# TSOC_USBUART2_R5_1.net
KiCad netlist of a schematic drawn in EAGLE
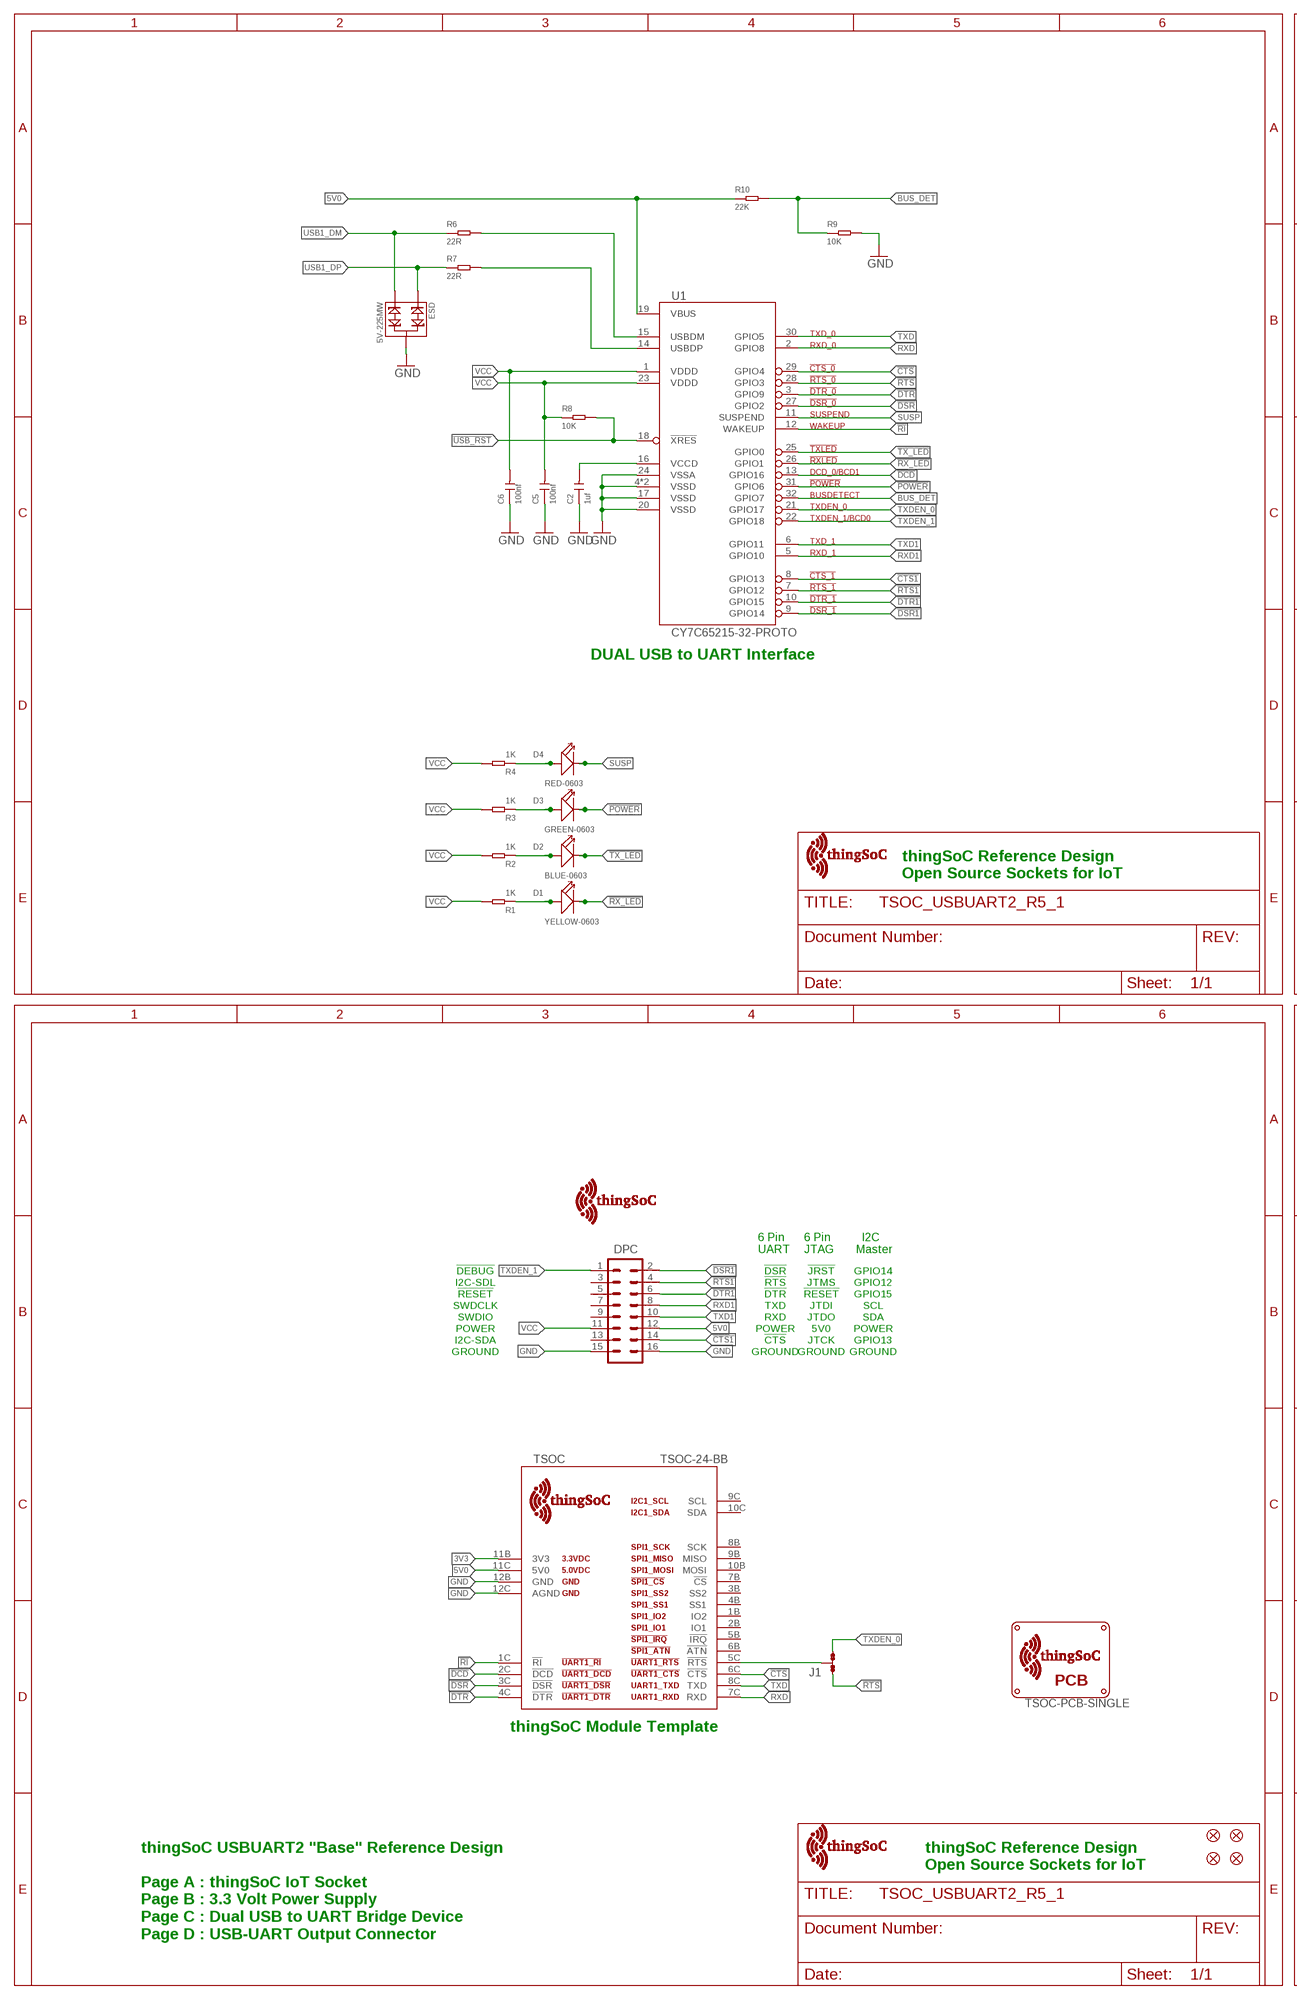
[diagram p0: schematic, sheet 1, part 1 of 2]
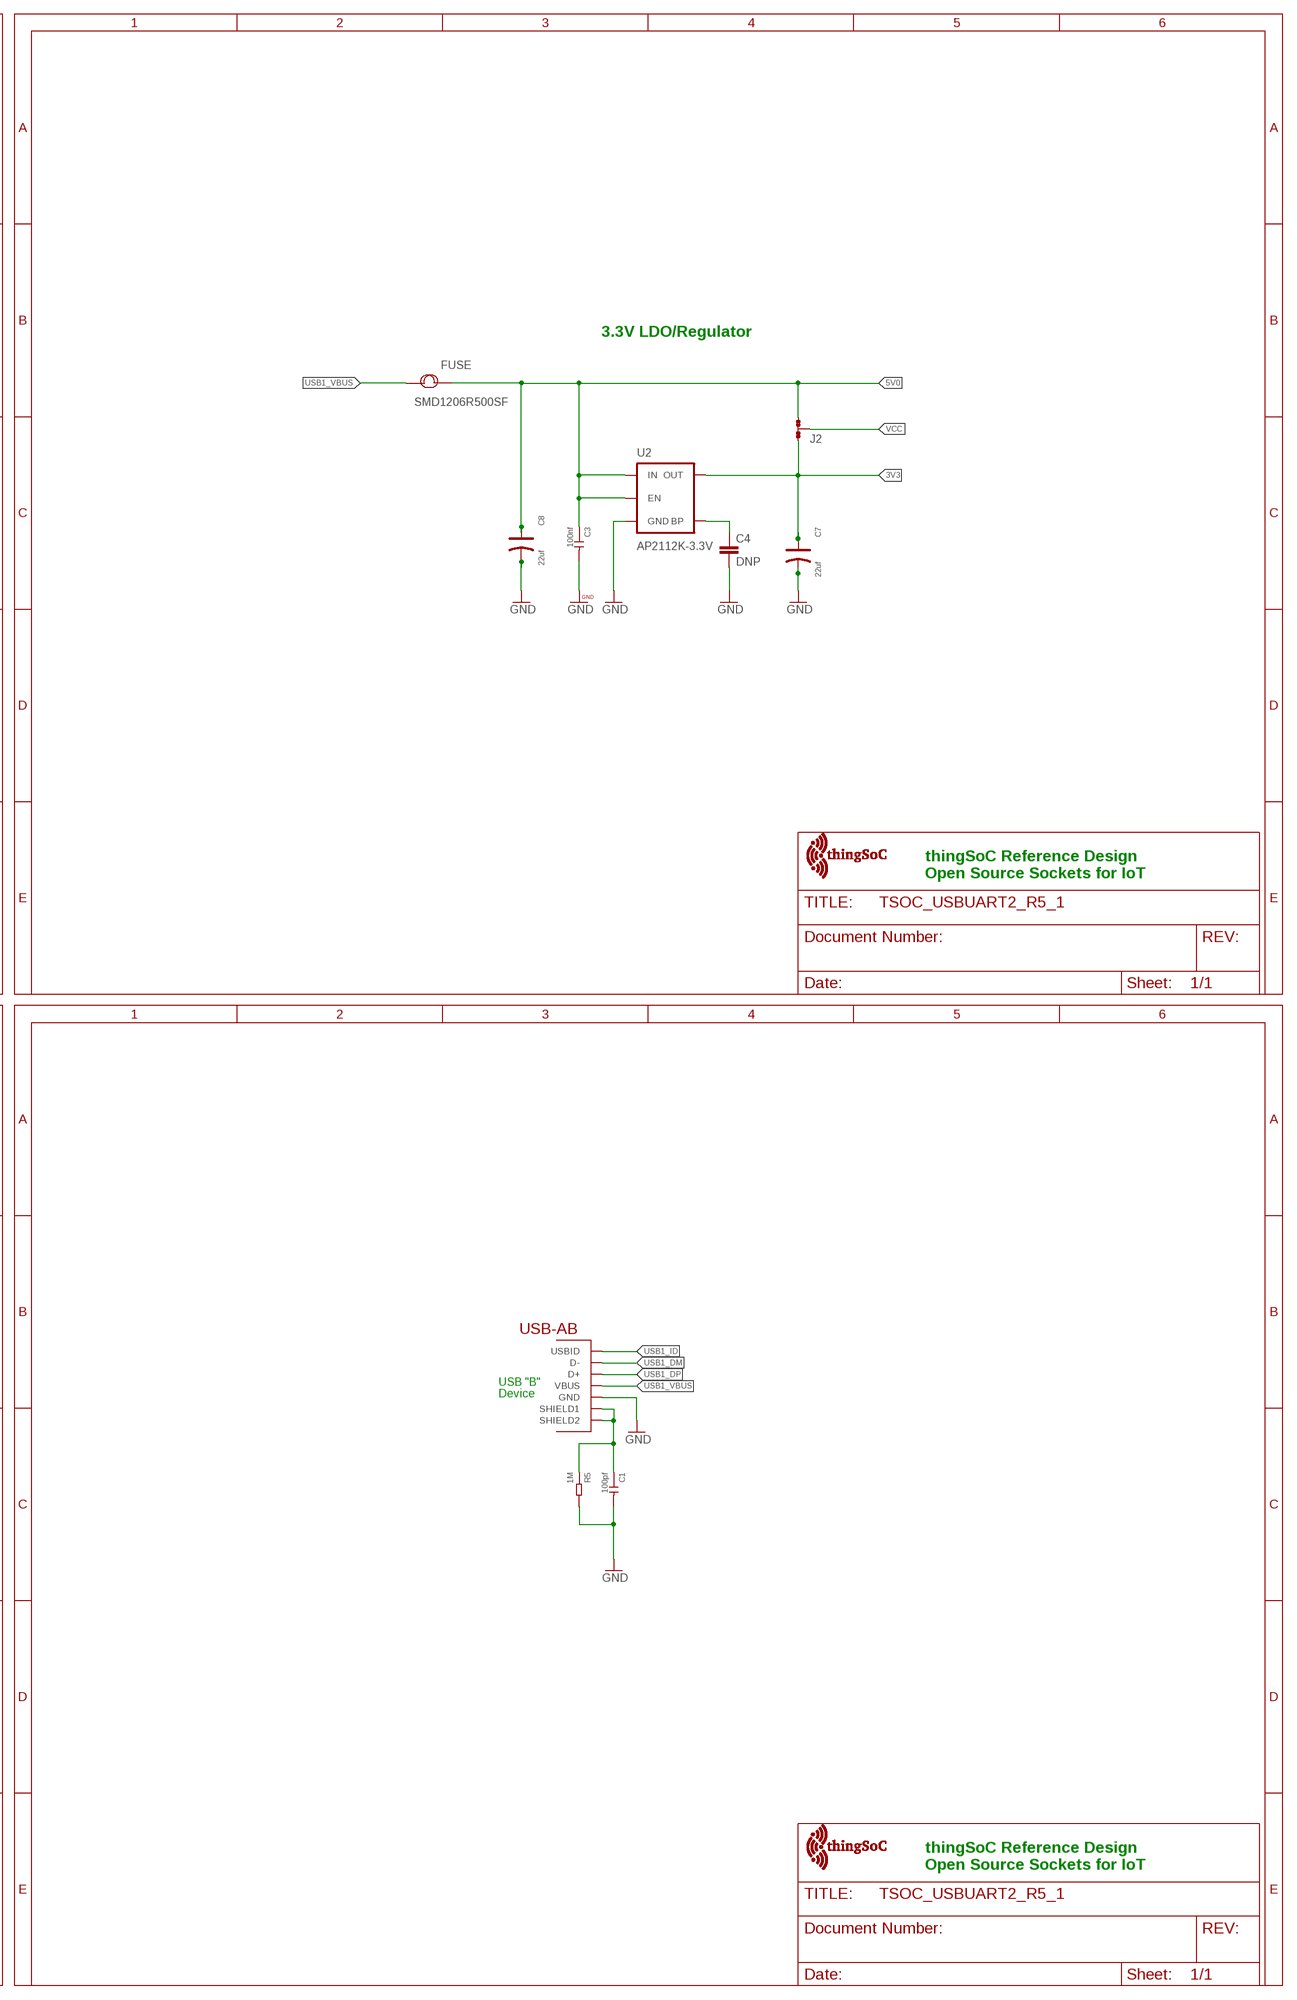
[diagram p1: schematic, sheet 1, part 2 of 2]

(export (version "E")
  (design (tool "Eeschema 10.0.6"))
  (components
    (comp (ref "$$U$2")
      (value "TSOC-LOGO")
      (footprint "eagle-import:TSOC-LOGO-BLANK")
      (libsource (lib "eagle-import") (part "TSOC-LOGO"))
    )
    (comp (ref "C1")
      (value "100pf")
      (footprint "eagle-import:C0603")
      (fields (field (name "MPN") "CC0603JRNPO9BN101"))
      (libsource (lib "eagle-import") (part "CERAMIC-100PF-50V-5%-NPO(0603)"))
    )
    (comp (ref "C2")
      (value "1uf")
      (footprint "eagle-import:C0603")
      (fields (field (name "MPN") "CC0603KRX7R8BB105"))
      (libsource (lib "eagle-import") (part "CERAMIC-1UF-25V-10%-X7R(0603)"))
    )
    (comp (ref "C3")
      (value "100nf")
      (footprint "eagle-import:C0603")
      (fields (field (name "MPN") "CC0603KRX7R9BB104"))
      (libsource (lib "eagle-import") (part "CERAMIC-100NF-50V-10%-X7R(0603)"))
    )
    (comp (ref "C4")
      (value "DNP")
      (footprint "eagle-import:EIA-0603")
      (libsource (lib "eagle-import") (part "CAP-0603"))
    )
    (comp (ref "C5")
      (value "100nf")
      (footprint "eagle-import:C0603")
      (fields (field (name "MPN") "CC0603KRX7R9BB104"))
      (libsource (lib "eagle-import") (part "CERAMIC-100NF-50V-10%-X7R(0603)"))
    )
    (comp (ref "C6")
      (value "100nf")
      (footprint "eagle-import:C0603")
      (fields (field (name "MPN") "CC0603KRX7R9BB104"))
      (libsource (lib "eagle-import") (part "CERAMIC-100NF-50V-10%-X7R(0603)"))
    )
    (comp (ref "C7")
      (value "22uf")
      (footprint "eagle-import:AVX-A")
      (fields (field (name "MPN") "TAJA226*010#NJ"))
      (libsource (lib "eagle-import") (part "TANTALUM-SMD-22UF-10V(AVX-A)"))
    )
    (comp (ref "C8")
      (value "22uf")
      (footprint "eagle-import:AVX-A")
      (fields (field (name "MPN") "TAJA226*010#NJ"))
      (libsource (lib "eagle-import") (part "TANTALUM-SMD-22UF-10V(AVX-A)"))
    )
    (comp (ref "D1")
      (value "YELLOW-0603")
      (footprint "eagle-import:LED-0603")
      (fields (field (name "MPN") "19-217-Y5C-AM1N1VY-3T"))
      (libsource (lib "eagle-import") (part "SMD-LED-CLEAR-YELLOW(0603)"))
    )
    (comp (ref "D2")
      (value "BLUE-0603")
      (footprint "eagle-import:LED-0603")
      (fields (field (name "MPN") "19-217-BHC-ZL1M2RY-3T"))
      (libsource (lib "eagle-import") (part "SMD-LED-CLEAR-BLUE(0603)"))
    )
    (comp (ref "D3")
      (value "GREEN-0603")
      (footprint "eagle-import:LED-0603")
      (fields (field (name "MPN") "19-217-G7C-AN1P2-3T"))
      (libsource (lib "eagle-import") (part "SMD-LED-CLEAR-GREEN(0603)"))
    )
    (comp (ref "D4")
      (value "RED-0603")
      (footprint "eagle-import:LED-0603")
      (fields (field (name "MPN") "19-217-R6C-AL1M2VY-3T"))
      (libsource (lib "eagle-import") (part "LED-SMD-RED-DIFFUSED(0603)"))
    )
    (comp (ref "DPC")
      (value "M08X2")
      (footprint "eagle-import:2X8")
      (libsource (lib "eagle-import") (part "M08X2"))
    )
    (comp (ref "ESD")
      (value "5V-225MW")
      (footprint "eagle-import:SOT-23")
      (fields (field (name "MPN") "CESD5V0AP"))
      (libsource (lib "eagle-import") (part "SMD-DIODE-TVS-5V-225MW(SOT-23)"))
    )
    (comp (ref "FID1")
      (value "FIDUCIALUFIDUCIAL")
      (footprint "eagle-import:MICRO-FIDUCIAL")
      (libsource (lib "eagle-import") (part "FIDUCIALUFIDUCIAL"))
    )
    (comp (ref "FID2")
      (value "FIDUCIALUFIDUCIAL")
      (footprint "eagle-import:MICRO-FIDUCIAL")
      (libsource (lib "eagle-import") (part "FIDUCIALUFIDUCIAL"))
    )
    (comp (ref "FID3")
      (value "FIDUCIALUFIDUCIAL")
      (footprint "eagle-import:MICRO-FIDUCIAL")
      (libsource (lib "eagle-import") (part "FIDUCIALUFIDUCIAL"))
    )
    (comp (ref "FID4")
      (value "FIDUCIALUFIDUCIAL")
      (footprint "eagle-import:MICRO-FIDUCIAL")
      (libsource (lib "eagle-import") (part "FIDUCIALUFIDUCIAL"))
    )
    (comp (ref "FUSE")
      (value "SMD1206R500SF")
      (footprint "eagle-import:F1206")
      (libsource (lib "eagle-import") (part "SMD-PPTC-500MA(1206)"))
    )
    (comp (ref "J1")
      (value "JMP-3-1_2")
      (footprint "eagle-import:JMP-3-1_2")
      (libsource (lib "eagle-import") (part "JMP-3-1_2"))
    )
    (comp (ref "J2")
      (value "JMP-3-1_2")
      (footprint "eagle-import:JMP-3-1_2")
      (libsource (lib "eagle-import") (part "JMP-3-1_2"))
    )
    (comp (ref "R1")
      (value "1K")
      (footprint "eagle-import:R0603")
      (fields (field (name "MPN") "RC0603FR-071KL"))
      (libsource (lib "eagle-import") (part "SMD-RES-1K-1%-1/10W(0603)"))
    )
    (comp (ref "R2")
      (value "1K")
      (footprint "eagle-import:R0603")
      (fields (field (name "MPN") "RC0603FR-071KL"))
      (libsource (lib "eagle-import") (part "SMD-RES-1K-1%-1/10W(0603)"))
    )
    (comp (ref "R3")
      (value "1K")
      (footprint "eagle-import:R0603")
      (fields (field (name "MPN") "RC0603FR-071KL"))
      (libsource (lib "eagle-import") (part "SMD-RES-1K-1%-1/10W(0603)"))
    )
    (comp (ref "R4")
      (value "1K")
      (footprint "eagle-import:R0603")
      (fields (field (name "MPN") "RC0603FR-071KL"))
      (libsource (lib "eagle-import") (part "SMD-RES-1K-1%-1/10W(0603)"))
    )
    (comp (ref "R5")
      (value "1M")
      (footprint "eagle-import:R0603")
      (fields (field (name "MPN") "RC0603FR-071ML"))
      (libsource (lib "eagle-import") (part "SMD-RES-1M-1%-1/10W(0603)"))
    )
    (comp (ref "R6")
      (value "22R")
      (footprint "eagle-import:R0603")
      (fields (field (name "MPN") "RC0603JR-0722RL"))
      (libsource (lib "eagle-import") (part "SMD-RES-22R-5%-1/10W(0603)"))
    )
    (comp (ref "R7")
      (value "22R")
      (footprint "eagle-import:R0603")
      (fields (field (name "MPN") "RC0603JR-0722RL"))
      (libsource (lib "eagle-import") (part "SMD-RES-22R-5%-1/10W(0603)"))
    )
    (comp (ref "R8")
      (value "10K")
      (footprint "eagle-import:R0603")
      (fields (field (name "MPN") "RC0603FR-0710KL"))
      (libsource (lib "eagle-import") (part "SMD-RES-10K-1%-1/10W(0603)"))
    )
    (comp (ref "R9")
      (value "10K")
      (footprint "eagle-import:R0603")
      (fields (field (name "MPN") "RC0603FR-0710KL"))
      (libsource (lib "eagle-import") (part "SMD-RES-10K-1%-1/10W(0603)"))
    )
    (comp (ref "R10")
      (value "22K")
      (footprint "eagle-import:R0603")
      (fields (field (name "MPN") "RC0603JR-0722KL"))
      (libsource (lib "eagle-import") (part "SMD-RES-22K-5%-1/10W(0603)"))
    )
    (comp (ref "TSOC")
      (value "TSOC-24-BB")
      (footprint "eagle-import:TSOC-BB-S24")
      (libsource (lib "eagle-import") (part "TSOC-24-BB"))
    )
    (comp (ref "U$1")
      (value "TSOC-LOGO")
      (footprint "eagle-import:TSOC-LOGO-BLANK")
      (libsource (lib "eagle-import") (part "TSOC-LOGO"))
    )
    (comp (ref "U$3")
      (value "TSOC-LOGO")
      (footprint "eagle-import:TSOC-LOGO-BLANK")
      (libsource (lib "eagle-import") (part "TSOC-LOGO"))
    )
    (comp (ref "U$4")
      (value "TSOC-PCB-SINGLE")
      (footprint "eagle-import:TSOC-BB-BRD-DIM")
      (libsource (lib "eagle-import") (part "TSOC-PCB-SINGLE"))
    )
    (comp (ref "U$7")
      (value "TSOC-LOGO-SMALL")
      (footprint "eagle-import:TSOC-LOGO-SML")
      (libsource (lib "eagle-import") (part "TSOC-LOGO-SMALL"))
    )
    (comp (ref "U$100")
      (value "TSOC-LOGO-LRG")
      (footprint "eagle-import:TSOC-LOGO-LRG")
      (libsource (lib "eagle-import") (part "TSOC-LOGO-LRG"))
    )
    (comp (ref "U1")
      (value "CY7C65215-32-PROTO")
      (footprint "eagle-import:QFN32-PROTO")
      (libsource (lib "eagle-import") (part "CY7C65215-32-PROTO"))
    )
    (comp (ref "U2")
      (value "AP2112K-3.3V")
      (footprint "eagle-import:SOT23-5")
      (libsource (lib "eagle-import") (part "V_REG_LDOSMD"))
    )
    (comp (ref "USB")
      (value "USB_AB")
      (footprint "eagle-import:USB-AB-MICRO-SMD")
      (libsource (lib "eagle-import") (part "USB_AB"))
    )
  )
  (nets
    (net (code "1") (name "/~{CTS1}") (class "Default")
      (node (ref "DPC") (pin "14") (pinfunction "14_14") (pintype "passive"))
      (node (ref "U1") (pin "8") (pinfunction "GPIO13_8") (pintype "input"))
    )
    (net (code "2") (name "/~{CTS}") (class "Default")
      (node (ref "TSOC") (pin "6C") (pinfunction "~{CTS}_6C") (pintype "bidirectional"))
      (node (ref "U1") (pin "29") (pinfunction "GPIO4_29") (pintype "input"))
    )
    (net (code "3") (name "/~{DCD}") (class "Default")
      (node (ref "TSOC") (pin "2C") (pinfunction "~{DCD}_2C") (pintype "bidirectional"))
      (node (ref "U1") (pin "13") (pinfunction "GPIO16_13") (pintype "output"))
    )
    (net (code "4") (name "/~{DSR1}") (class "Default")
      (node (ref "DPC") (pin "2") (pinfunction "2_2") (pintype "passive"))
      (node (ref "U1") (pin "9") (pinfunction "GPIO14_9") (pintype "input"))
    )
    (net (code "5") (name "/~{DSR}") (class "Default")
      (node (ref "TSOC") (pin "3C") (pinfunction "~{DSR}_3C") (pintype "bidirectional"))
      (node (ref "U1") (pin "27") (pinfunction "GPIO2_27") (pintype "input"))
    )
    (net (code "6") (name "/~{DTR1}") (class "Default")
      (node (ref "DPC") (pin "6") (pinfunction "6_6") (pintype "passive"))
      (node (ref "U1") (pin "10") (pinfunction "GPIO15_10") (pintype "output"))
    )
    (net (code "7") (name "/~{DTR}") (class "Default")
      (node (ref "TSOC") (pin "4C") (pinfunction "~{DTR}_4C") (pintype "bidirectional"))
      (node (ref "U1") (pin "3") (pinfunction "GPIO9_3") (pintype "output"))
    )
    (net (code "8") (name "/~{POWER}") (class "Default")
      (node (ref "D3") (pin "-") (pinfunction "-_-") (pintype "passive"))
      (node (ref "U1") (pin "31") (pinfunction "GPIO6_31") (pintype "input"))
    )
    (net (code "9") (name "/~{RI}") (class "Default")
      (node (ref "TSOC") (pin "1C") (pinfunction "~{RI}_1C") (pintype "bidirectional"))
      (node (ref "U1") (pin "12") (pinfunction "WAKEUP_12") (pintype "input"))
    )
    (net (code "10") (name "/~{RTS1}") (class "Default")
      (node (ref "DPC") (pin "4") (pinfunction "4_4") (pintype "passive"))
      (node (ref "U1") (pin "7") (pinfunction "GPIO12_7") (pintype "output"))
    )
    (net (code "11") (name "/~{RTS}") (class "Default")
      (node (ref "J1") (pin "1") (pinfunction "1_1") (pintype "passive"))
      (node (ref "U1") (pin "28") (pinfunction "GPIO3_28") (pintype "output"))
    )
    (net (code "12") (name "/~{RX_LED}") (class "Default")
      (node (ref "D1") (pin "-") (pinfunction "-_-") (pintype "passive"))
      (node (ref "U1") (pin "26") (pinfunction "GPIO1_26") (pintype "input"))
    )
    (net (code "13") (name "/~{TX_LED}") (class "Default")
      (node (ref "D2") (pin "-") (pinfunction "-_-") (pintype "passive"))
      (node (ref "U1") (pin "25") (pinfunction "GPIO0_25") (pintype "input"))
    )
    (net (code "14") (name "/~{USB_RST}") (class "Default")
      (node (ref "R8") (pin "2") (pinfunction "2_2") (pintype "passive"))
      (node (ref "U1") (pin "18") (pinfunction "~{XRES}_18") (pintype "input"))
    )
    (net (code "15") (name "3V3") (class "Default")
      (node (ref "C7") (pin "+") (pinfunction "+_+") (pintype "passive"))
      (node (ref "J2") (pin "1") (pinfunction "1_1") (pintype "passive"))
      (node (ref "TSOC") (pin "11B") (pinfunction "3V3_11B") (pintype "bidirectional"))
      (node (ref "U2") (pin "5") (pinfunction "OUT_5") (pintype "passive"))
    )
    (net (code "16") (name "5V0") (class "Default")
      (node (ref "C3") (pin "1") (pinfunction "1_1") (pintype "passive"))
      (node (ref "C8") (pin "+") (pinfunction "+_+") (pintype "passive"))
      (node (ref "DPC") (pin "12") (pinfunction "12_12") (pintype "passive"))
      (node (ref "FUSE") (pin "2") (pinfunction "2_2") (pintype "bidirectional"))
      (node (ref "J2") (pin "3") (pinfunction "3_3") (pintype "passive"))
      (node (ref "R10") (pin "1") (pinfunction "1_1") (pintype "passive"))
      (node (ref "TSOC") (pin "11C") (pinfunction "5V0_11C") (pintype "bidirectional"))
      (node (ref "U1") (pin "19") (pinfunction "VBUS_19") (pintype "power_in"))
      (node (ref "U2") (pin "1") (pinfunction "IN_1") (pintype "input"))
      (node (ref "U2") (pin "3") (pinfunction "EN_3") (pintype "input"))
    )
    (net (code "17") (name "BUS_DET") (class "Default")
      (node (ref "R10") (pin "2") (pinfunction "2_2") (pintype "passive"))
      (node (ref "R9") (pin "1") (pinfunction "1_1") (pintype "passive"))
      (node (ref "U1") (pin "32") (pinfunction "GPIO7_32") (pintype "input"))
    )
    (net (code "18") (name "GND") (class "Default")
      (node (ref "C1") (pin "2") (pinfunction "2_2") (pintype "passive"))
      (node (ref "C2") (pin "1") (pinfunction "1_1") (pintype "passive"))
      (node (ref "C3") (pin "2") (pinfunction "2_2") (pintype "passive"))
      (node (ref "C4") (pin "2") (pinfunction "2_2") (pintype "passive"))
      (node (ref "C5") (pin "1") (pinfunction "1_1") (pintype "passive"))
      (node (ref "C6") (pin "1") (pinfunction "1_1") (pintype "passive"))
      (node (ref "C7") (pin "-") (pinfunction "-_-") (pintype "passive"))
      (node (ref "C8") (pin "-") (pinfunction "-_-") (pintype "passive"))
      (node (ref "DPC") (pin "15") (pinfunction "15_15") (pintype "passive"))
      (node (ref "DPC") (pin "16") (pinfunction "16_16") (pintype "passive"))
      (node (ref "ESD") (pin "3") (pinfunction "3_3") (pintype "bidirectional"))
      (node (ref "R5") (pin "2") (pinfunction "2_2") (pintype "passive"))
      (node (ref "R9") (pin "2") (pinfunction "2_2") (pintype "passive"))
      (node (ref "TSOC") (pin "12B") (pinfunction "GND_12B") (pintype "bidirectional"))
      (node (ref "TSOC") (pin "12C") (pinfunction "AGND_12C") (pintype "bidirectional"))
      (node (ref "U1") (pin "17") (pinfunction "VSSD_17") (pintype "power_in"))
      (node (ref "U1") (pin "20") (pinfunction "VSSD_20") (pintype "power_in"))
      (node (ref "U1") (pin "24") (pinfunction "VSSA_24") (pintype "power_in"))
      (node (ref "U1") (pin "4") (pinfunction "VSSD_4") (pintype "power_in"))
      (node (ref "U1") (pin "EXP") (pinfunction "VSSD_EXP") (pintype "power_in"))
      (node (ref "U2") (pin "2") (pinfunction "GND_2") (pintype "input"))
      (node (ref "USB") (pin "GND") (pinfunction "GND_GND") (pintype "bidirectional"))
    )
    (net (code "19") (name "Net-(C1-Pad1)") (class "Default")
      (node (ref "C1") (pin "1") (pinfunction "1_1") (pintype "passive"))
      (node (ref "R5") (pin "1") (pinfunction "1_1") (pintype "passive"))
      (node (ref "USB") (pin "SHIELD1") (pinfunction "SHIELD1_SHIELD1") (pintype "bidirectional"))
      (node (ref "USB") (pin "SHIELD2") (pinfunction "SHIELD2_SHIELD2") (pintype "bidirectional"))
    )
    (net (code "20") (name "Net-(D1-Pad+)") (class "Default")
      (node (ref "D1") (pin "+") (pinfunction "+_+") (pintype "passive"))
      (node (ref "R1") (pin "1") (pinfunction "1_1") (pintype "passive"))
    )
    (net (code "21") (name "Net-(D2-Pad+)") (class "Default")
      (node (ref "D2") (pin "+") (pinfunction "+_+") (pintype "passive"))
      (node (ref "R2") (pin "1") (pinfunction "1_1") (pintype "passive"))
    )
    (net (code "22") (name "Net-(D3-Pad+)") (class "Default")
      (node (ref "D3") (pin "+") (pinfunction "+_+") (pintype "passive"))
      (node (ref "R3") (pin "1") (pinfunction "1_1") (pintype "passive"))
    )
    (net (code "23") (name "Net-(D4-Pad+)") (class "Default")
      (node (ref "D4") (pin "+") (pinfunction "+_+") (pintype "passive"))
      (node (ref "R4") (pin "1") (pinfunction "1_1") (pintype "passive"))
    )
    (net (code "24") (name "Net-(TSOC-~{RTS})") (class "Default")
      (node (ref "J1") (pin "2") (pinfunction "2_2") (pintype "passive"))
      (node (ref "TSOC") (pin "5C") (pinfunction "~{RTS}_5C") (pintype "bidirectional"))
    )
    (net (code "25") (name "Net-(U1-USBDM)") (class "Default")
      (node (ref "R6") (pin "2") (pinfunction "2_2") (pintype "passive"))
      (node (ref "U1") (pin "15") (pinfunction "USBDM_15") (pintype "bidirectional"))
    )
    (net (code "26") (name "Net-(U1-USBDP)") (class "Default")
      (node (ref "R7") (pin "2") (pinfunction "2_2") (pintype "passive"))
      (node (ref "U1") (pin "14") (pinfunction "USBDP_14") (pintype "bidirectional"))
    )
    (net (code "27") (name "Net-(U1-VCCD)") (class "Default")
      (node (ref "C2") (pin "2") (pinfunction "2_2") (pintype "passive"))
      (node (ref "U1") (pin "16") (pinfunction "VCCD_16") (pintype "output"))
    )
    (net (code "28") (name "Net-(U2-BP)") (class "Default")
      (node (ref "C4") (pin "1") (pinfunction "1_1") (pintype "passive"))
      (node (ref "U2") (pin "4") (pinfunction "BP_4") (pintype "input"))
    )
    (net (code "29") (name "RXD") (class "Default")
      (node (ref "TSOC") (pin "7C") (pinfunction "RXD_7C") (pintype "bidirectional"))
      (node (ref "U1") (pin "2") (pinfunction "GPIO8_2") (pintype "input"))
    )
    (net (code "30") (name "RXD1") (class "Default")
      (node (ref "DPC") (pin "8") (pinfunction "8_8") (pintype "passive"))
      (node (ref "U1") (pin "5") (pinfunction "GPIO10_5") (pintype "input"))
    )
    (net (code "31") (name "SUSP") (class "Default")
      (node (ref "D4") (pin "-") (pinfunction "-_-") (pintype "passive"))
      (node (ref "U1") (pin "11") (pinfunction "SUSPEND_11") (pintype "input"))
    )
    (net (code "32") (name "TXD") (class "Default")
      (node (ref "TSOC") (pin "8C") (pinfunction "TXD_8C") (pintype "bidirectional"))
      (node (ref "U1") (pin "30") (pinfunction "GPIO5_30") (pintype "output"))
    )
    (net (code "33") (name "TXD1") (class "Default")
      (node (ref "DPC") (pin "10") (pinfunction "10_10") (pintype "passive"))
      (node (ref "U1") (pin "6") (pinfunction "GPIO11_6") (pintype "output"))
    )
    (net (code "34") (name "TXDEN_0") (class "Default")
      (node (ref "J1") (pin "3") (pinfunction "3_3") (pintype "passive"))
      (node (ref "U1") (pin "21") (pinfunction "GPIO17_21") (pintype "input"))
    )
    (net (code "35") (name "TXDEN_1") (class "Default")
      (node (ref "DPC") (pin "1") (pinfunction "1_1") (pintype "passive"))
      (node (ref "U1") (pin "22") (pinfunction "GPIO18_22") (pintype "input"))
    )
    (net (code "36") (name "USB1_DM") (class "Default")
      (node (ref "ESD") (pin "2") (pinfunction "2_2") (pintype "power_in"))
      (node (ref "R6") (pin "1") (pinfunction "1_1") (pintype "passive"))
      (node (ref "USB") (pin "D-") (pinfunction "D-_D-") (pintype "bidirectional"))
    )
    (net (code "37") (name "USB1_DP") (class "Default")
      (node (ref "ESD") (pin "1") (pinfunction "1_1") (pintype "power_in"))
      (node (ref "R7") (pin "1") (pinfunction "1_1") (pintype "passive"))
      (node (ref "USB") (pin "D+") (pinfunction "D+_D+") (pintype "bidirectional"))
    )
    (net (code "38") (name "USB1_ID") (class "Default")
      (node (ref "USB") (pin "ID") (pinfunction "USBID_ID") (pintype "bidirectional"))
    )
    (net (code "39") (name "USB1_VBUS") (class "Default")
      (node (ref "FUSE") (pin "1") (pinfunction "1_1") (pintype "bidirectional"))
      (node (ref "USB") (pin "VBUS") (pinfunction "VBUS_VBUS") (pintype "bidirectional"))
    )
    (net (code "40") (name "VCC") (class "Default")
      (node (ref "C5") (pin "2") (pinfunction "2_2") (pintype "passive"))
      (node (ref "C6") (pin "2") (pinfunction "2_2") (pintype "passive"))
      (node (ref "DPC") (pin "11") (pinfunction "11_11") (pintype "passive"))
      (node (ref "J2") (pin "2") (pinfunction "2_2") (pintype "passive"))
      (node (ref "R1") (pin "2") (pinfunction "2_2") (pintype "passive"))
      (node (ref "R2") (pin "2") (pinfunction "2_2") (pintype "passive"))
      (node (ref "R3") (pin "2") (pinfunction "2_2") (pintype "passive"))
      (node (ref "R4") (pin "2") (pinfunction "2_2") (pintype "passive"))
      (node (ref "R8") (pin "1") (pinfunction "1_1") (pintype "passive"))
      (node (ref "U1") (pin "1") (pinfunction "VDDD_1") (pintype "power_in"))
      (node (ref "U1") (pin "23") (pinfunction "VDDD_23") (pintype "power_in"))
    )
    (net (code "41") (name "unconnected-(DPC-Pad3)") (class "Default")
      (node (ref "DPC") (pin "3") (pinfunction "3_3") (pintype "passive"))
    )
    (net (code "42") (name "unconnected-(DPC-Pad5)") (class "Default")
      (node (ref "DPC") (pin "5") (pinfunction "5_5") (pintype "passive"))
    )
    (net (code "43") (name "unconnected-(DPC-Pad7)") (class "Default")
      (node (ref "DPC") (pin "7") (pinfunction "7_7") (pintype "passive"))
    )
    (net (code "44") (name "unconnected-(DPC-Pad9)") (class "Default")
      (node (ref "DPC") (pin "9") (pinfunction "9_9") (pintype "passive"))
    )
    (net (code "45") (name "unconnected-(DPC-Pad13)") (class "Default")
      (node (ref "DPC") (pin "13") (pinfunction "13_13") (pintype "passive"))
    )
    (net (code "46") (name "unconnected-(TSOC-IO1-Pad2B)") (class "Default")
      (node (ref "TSOC") (pin "2B") (pinfunction "IO1_2B") (pintype "bidirectional"))
    )
    (net (code "47") (name "unconnected-(TSOC-IO2-Pad1B)") (class "Default")
      (node (ref "TSOC") (pin "1B") (pinfunction "IO2_1B") (pintype "bidirectional"))
    )
    (net (code "48") (name "unconnected-(TSOC-MISO-Pad9B)") (class "Default")
      (node (ref "TSOC") (pin "9B") (pinfunction "MISO_9B") (pintype "bidirectional"))
    )
    (net (code "49") (name "unconnected-(TSOC-MOSI-Pad10B)") (class "Default")
      (node (ref "TSOC") (pin "10B") (pinfunction "MOSI_10B") (pintype "bidirectional"))
    )
    (net (code "50") (name "unconnected-(TSOC-SCK-Pad8B)") (class "Default")
      (node (ref "TSOC") (pin "8B") (pinfunction "SCK_8B") (pintype "bidirectional"))
    )
    (net (code "51") (name "unconnected-(TSOC-SCL-Pad9C)") (class "Default")
      (node (ref "TSOC") (pin "9C") (pinfunction "SCL_9C") (pintype "bidirectional"))
    )
    (net (code "52") (name "unconnected-(TSOC-SDA-Pad10C)") (class "Default")
      (node (ref "TSOC") (pin "10C") (pinfunction "SDA_10C") (pintype "bidirectional"))
    )
    (net (code "53") (name "unconnected-(TSOC-SS1-Pad4B)") (class "Default")
      (node (ref "TSOC") (pin "4B") (pinfunction "SS1_4B") (pintype "bidirectional"))
    )
    (net (code "54") (name "unconnected-(TSOC-SS2-Pad3B)") (class "Default")
      (node (ref "TSOC") (pin "3B") (pinfunction "SS2_3B") (pintype "bidirectional"))
    )
    (net (code "55") (name "unconnected-(TSOC-~{ATN}-Pad6B)") (class "Default")
      (node (ref "TSOC") (pin "6B") (pinfunction "~{ATN}_6B") (pintype "bidirectional"))
    )
    (net (code "56") (name "unconnected-(TSOC-~{CS}-Pad7B)") (class "Default")
      (node (ref "TSOC") (pin "7B") (pinfunction "~{CS}_7B") (pintype "bidirectional"))
    )
    (net (code "57") (name "unconnected-(TSOC-~{IRQ}-Pad5B)") (class "Default")
      (node (ref "TSOC") (pin "5B") (pinfunction "~{IRQ}_5B") (pintype "bidirectional"))
    )
  )
)
